# Sheet1.net
KiCad netlist of a schematic drawn in Altium Designer
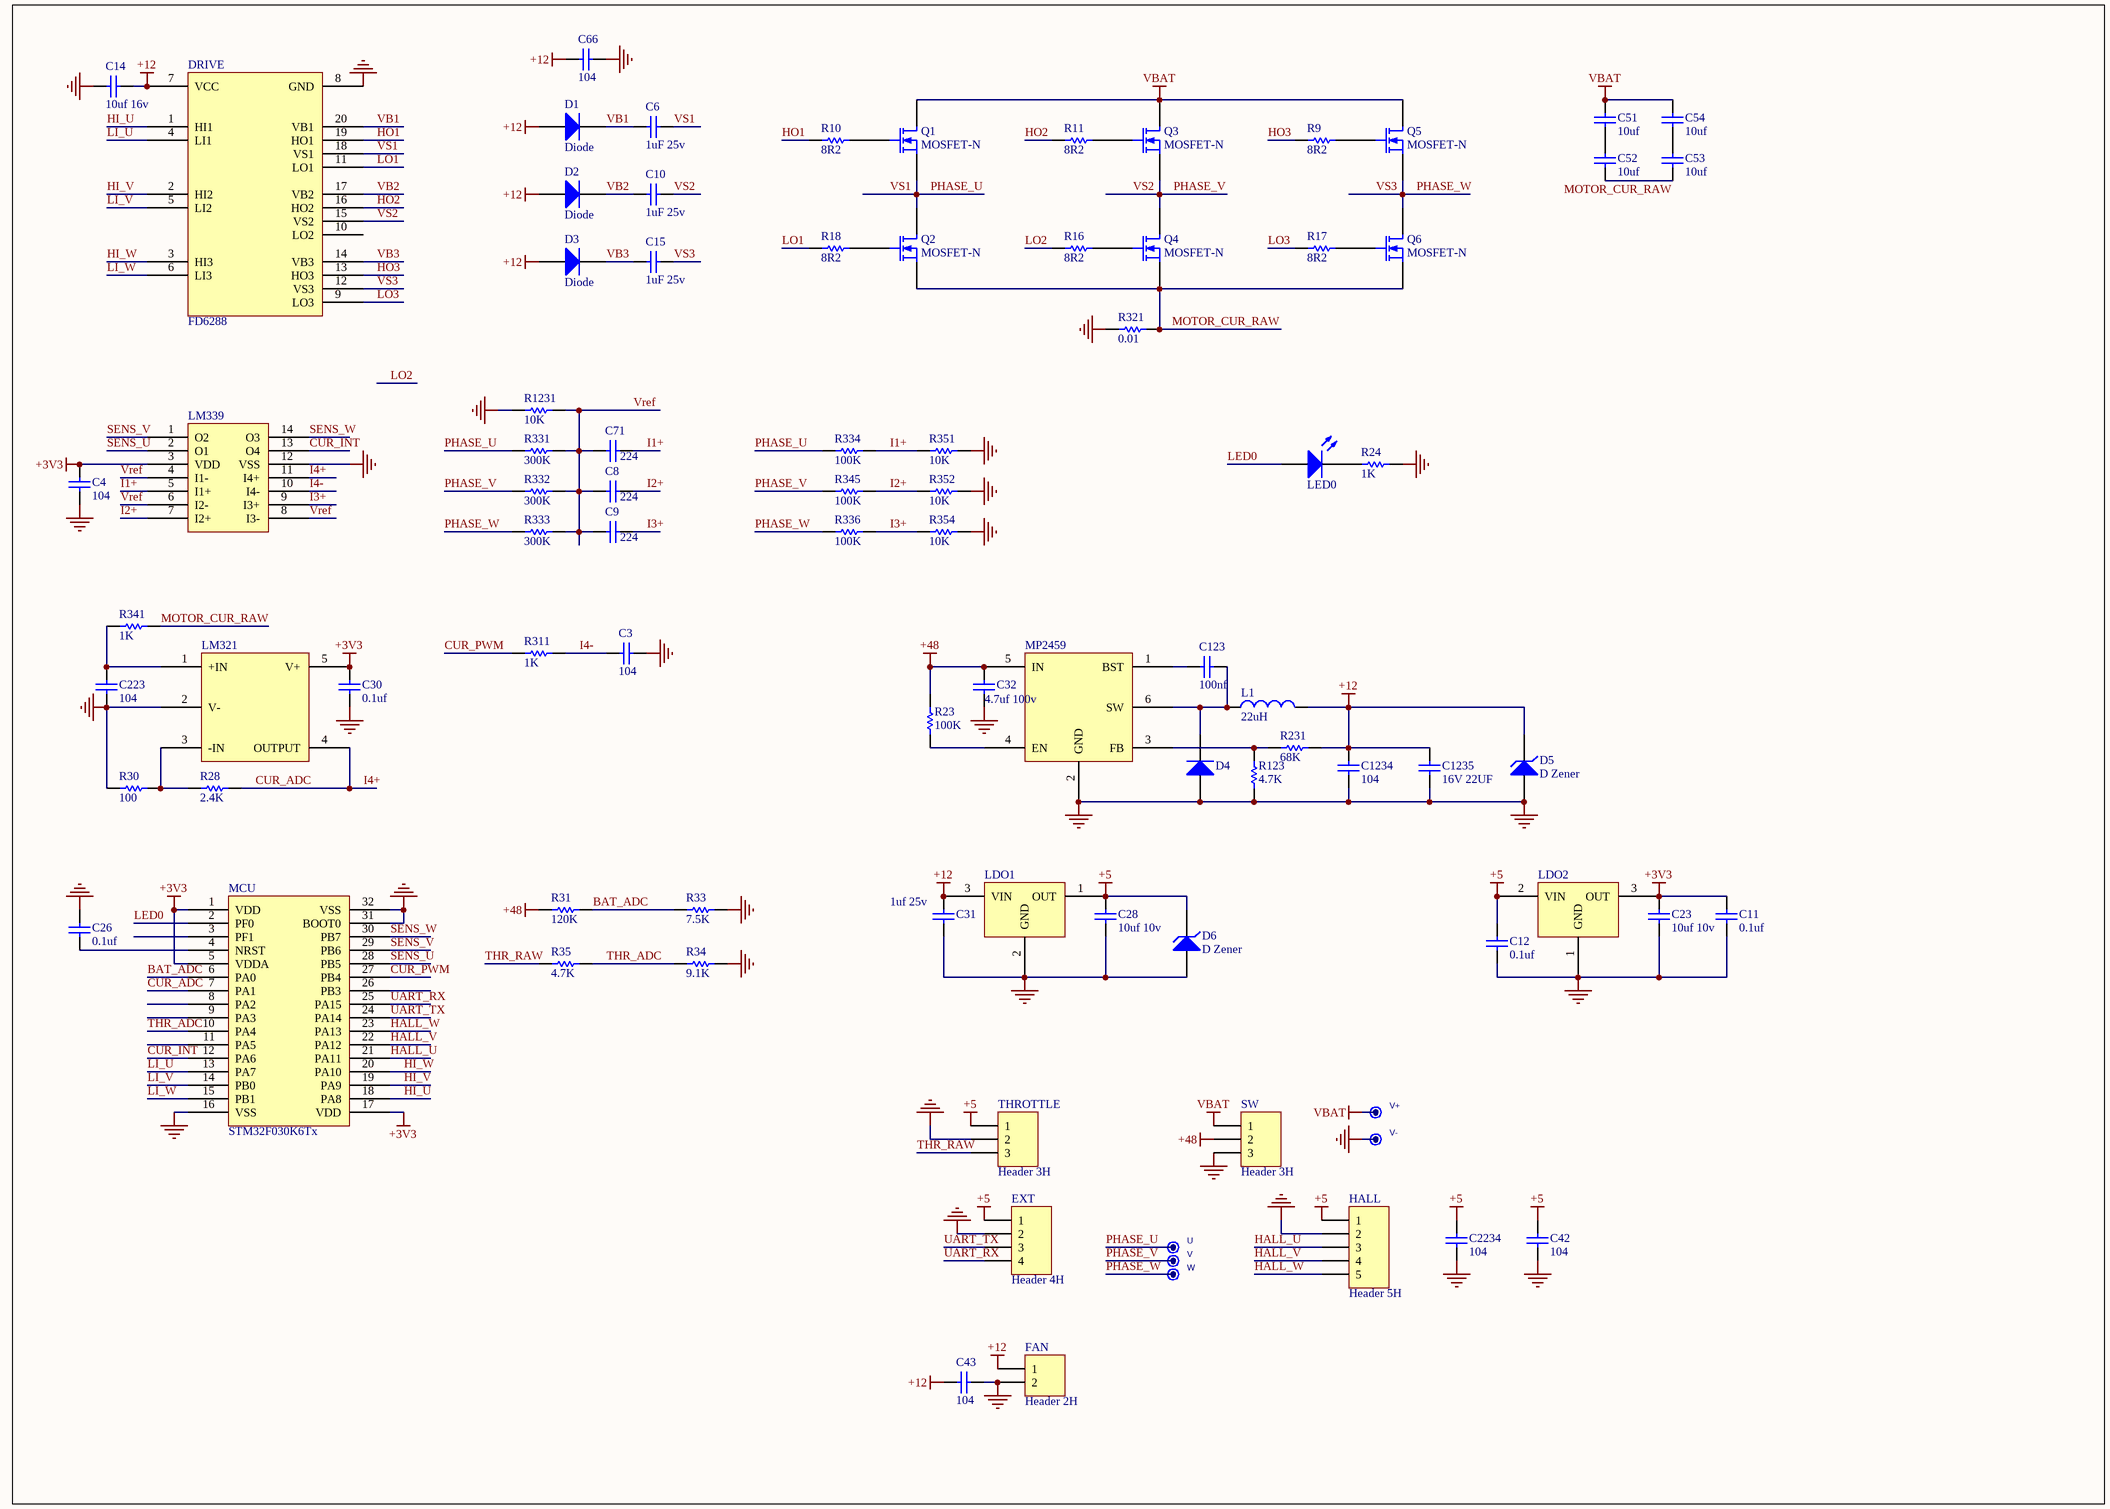
[diagram p0: Sheet1.SchDoc]

(export (version "E")
  (design (tool "Eeschema 10.0.6"))
  (components
    (comp (ref "C3")
      (value "104")
      (footprint "0603")
      (description "Capacitor")
      (fields (field (name "Comment") "Cap") (field (name "PUBLISHER") "Altium Limited"))
      (libsource (lib "Miscellaneous Devices") (part "Cap"))
    )
    (comp (ref "C4")
      (value "104")
      (footprint "0603")
      (description "Capacitor")
      (fields (field (name "Comment") "Cap") (field (name "PUBLISHER") "Altium Limited"))
      (libsource (lib "Miscellaneous Devices") (part "Cap"))
    )
    (comp (ref "C6")
      (value "1uF 25v")
      (footprint "0603")
      (description "Capacitor")
      (fields (field (name "Comment") "Cap") (field (name "PUBLISHER") "Altium Limited"))
      (libsource (lib "Miscellaneous Devices") (part "Cap"))
    )
    (comp (ref "C8")
      (value "224")
      (footprint "0603")
      (description "Capacitor")
      (fields (field (name "Comment") "Cap") (field (name "PUBLISHER") "Altium Limited"))
      (libsource (lib "Miscellaneous Devices") (part "Cap"))
    )
    (comp (ref "C9")
      (value "224")
      (footprint "0603")
      (description "Capacitor")
      (fields (field (name "Comment") "Cap") (field (name "PUBLISHER") "Altium Limited"))
      (libsource (lib "Miscellaneous Devices") (part "Cap"))
    )
    (comp (ref "C10")
      (value "1uF 25v")
      (footprint "0603")
      (description "Capacitor")
      (fields (field (name "Comment") "Cap") (field (name "PUBLISHER") "Altium Limited"))
      (libsource (lib "Miscellaneous Devices") (part "Cap"))
    )
    (comp (ref "C11")
      (value "0.1uf")
      (footprint "0603")
      (description "Capacitor")
      (fields (field (name "Comment") "Cap") (field (name "PUBLISHER") "Altium Limited"))
      (libsource (lib "Miscellaneous Devices") (part "Cap"))
    )
    (comp (ref "C12")
      (value "0.1uf")
      (footprint "0603")
      (description "Capacitor")
      (fields (field (name "Comment") "Cap") (field (name "PUBLISHER") "Altium Limited"))
      (libsource (lib "Miscellaneous Devices") (part "Cap"))
    )
    (comp (ref "C14")
      (value "10uf 16v")
      (footprint "0603")
      (description "Capacitor")
      (fields (field (name "Comment") "Cap") (field (name "PUBLISHER") "Altium Limited"))
      (libsource (lib "Miscellaneous Devices") (part "Cap"))
    )
    (comp (ref "C15")
      (value "1uF 25v")
      (footprint "0603")
      (description "Capacitor")
      (fields (field (name "Comment") "Cap") (field (name "PUBLISHER") "Altium Limited"))
      (libsource (lib "Miscellaneous Devices") (part "Cap"))
    )
    (comp (ref "C23")
      (value "10uf 10v")
      (footprint "0603")
      (description "Capacitor")
      (fields (field (name "Comment") "Cap") (field (name "PUBLISHER") "Altium Limited"))
      (libsource (lib "Miscellaneous Devices") (part "Cap"))
    )
    (comp (ref "C26")
      (value "0.1uf")
      (footprint "0603")
      (description "Capacitor")
      (fields (field (name "Comment") "Cap") (field (name "PUBLISHER") "Altium Limited"))
      (libsource (lib "Miscellaneous Devices") (part "Cap"))
    )
    (comp (ref "C28")
      (value "10uf 10v")
      (footprint "0603")
      (description "Capacitor")
      (fields (field (name "Comment") "Cap") (field (name "PUBLISHER") "Altium Limited"))
      (libsource (lib "Miscellaneous Devices") (part "Cap"))
    )
    (comp (ref "C30")
      (value "0.1uf")
      (footprint "0603")
      (description "Capacitor")
      (fields (field (name "Comment") "Cap") (field (name "PUBLISHER") "Altium Limited"))
      (libsource (lib "Miscellaneous Devices") (part "Cap"))
    )
    (comp (ref "C31")
      (value "1uf 25v")
      (footprint "0603")
      (description "Capacitor")
      (fields (field (name "Comment") "Cap") (field (name "PUBLISHER") "Altium Limited"))
      (libsource (lib "Miscellaneous Devices") (part "Cap"))
    )
    (comp (ref "C32")
      (value "4.7uf 100v")
      (footprint "1206")
      (description "Capacitor")
      (fields (field (name "Comment") "Cap") (field (name "PUBLISHER") "Altium Limited"))
      (libsource (lib "Miscellaneous Devices") (part "Cap"))
    )
    (comp (ref "C42")
      (value "104")
      (footprint "0603")
      (description "Capacitor")
      (fields (field (name "Comment") "Cap") (field (name "PUBLISHER") "Altium Limited"))
      (libsource (lib "Miscellaneous Devices") (part "Cap"))
    )
    (comp (ref "C43")
      (value "104")
      (footprint "0603")
      (description "Capacitor")
      (fields (field (name "Comment") "Cap") (field (name "PUBLISHER") "Altium Limited"))
      (libsource (lib "Miscellaneous Devices") (part "Cap"))
    )
    (comp (ref "C51")
      (value "10uf")
      (footprint "1206")
      (description "Capacitor")
      (fields (field (name "Comment") "Cap") (field (name "PUBLISHER") "Altium Limited"))
      (libsource (lib "Miscellaneous Devices") (part "Cap"))
    )
    (comp (ref "C52")
      (value "10uf")
      (footprint "1206")
      (description "Capacitor")
      (fields (field (name "Comment") "Cap") (field (name "PUBLISHER") "Altium Limited"))
      (libsource (lib "Miscellaneous Devices") (part "Cap"))
    )
    (comp (ref "C53")
      (value "10uf")
      (footprint "1206")
      (description "Capacitor")
      (fields (field (name "Comment") "Cap") (field (name "PUBLISHER") "Altium Limited"))
      (libsource (lib "Miscellaneous Devices") (part "Cap"))
    )
    (comp (ref "C54")
      (value "10uf")
      (footprint "1206")
      (description "Capacitor")
      (fields (field (name "Comment") "Cap") (field (name "PUBLISHER") "Altium Limited"))
      (libsource (lib "Miscellaneous Devices") (part "Cap"))
    )
    (comp (ref "C66")
      (value "104")
      (footprint "0603")
      (description "Capacitor")
      (fields (field (name "Comment") "Cap") (field (name "PUBLISHER") "Altium Limited"))
      (libsource (lib "Miscellaneous Devices") (part "Cap"))
    )
    (comp (ref "C71")
      (value "224")
      (footprint "0603")
      (description "Capacitor")
      (fields (field (name "Comment") "Cap") (field (name "PUBLISHER") "Altium Limited"))
      (libsource (lib "Miscellaneous Devices") (part "Cap"))
    )
    (comp (ref "C123")
      (value "100nf")
      (footprint "0603")
      (description "Capacitor")
      (fields (field (name "Comment") "Cap") (field (name "PUBLISHER") "Altium Limited"))
      (libsource (lib "Miscellaneous Devices") (part "Cap"))
    )
    (comp (ref "C223")
      (value "104")
      (footprint "0603")
      (description "Capacitor")
      (fields (field (name "Comment") "Cap") (field (name "PUBLISHER") "Altium Limited"))
      (libsource (lib "Miscellaneous Devices") (part "Cap"))
    )
    (comp (ref "C1234")
      (value "104")
      (footprint "0603")
      (description "Capacitor")
      (fields (field (name "Comment") "Cap") (field (name "PUBLISHER") "Altium Limited"))
      (libsource (lib "Miscellaneous Devices") (part "Cap"))
    )
    (comp (ref "C1235")
      (value "16V 22UF")
      (footprint "1206")
      (description "Capacitor")
      (fields (field (name "Comment") "Cap") (field (name "PUBLISHER") "Altium Limited"))
      (libsource (lib "Miscellaneous Devices") (part "Cap"))
    )
    (comp (ref "C2234")
      (value "104")
      (footprint "0603")
      (description "Capacitor")
      (fields (field (name "Comment") "Cap") (field (name "PUBLISHER") "Altium Limited"))
      (libsource (lib "Miscellaneous Devices") (part "Cap"))
    )
    (comp (ref "D1")
      (value "Diode")
      (footprint "0603")
      (description "Default Diode")
      (fields (field (name "PUBLISHER") "Altium Limited"))
      (libsource (lib "Miscellaneous Devices") (part "Diode"))
    )
    (comp (ref "D2")
      (value "Diode")
      (footprint "0603")
      (description "Default Diode")
      (fields (field (name "PUBLISHER") "Altium Limited"))
      (libsource (lib "Miscellaneous Devices") (part "Diode"))
    )
    (comp (ref "D3")
      (value "Diode")
      (footprint "0603")
      (description "Default Diode")
      (fields (field (name "PUBLISHER") "Altium Limited"))
      (libsource (lib "Miscellaneous Devices") (part "Diode"))
    )
    (comp (ref "D4")
      (value "Diode")
      (footprint "1206")
      (description "Default Diode")
      (fields (field (name "PUBLISHER") "Altium Limited"))
      (libsource (lib "Miscellaneous Devices") (part "Diode"))
    )
    (comp (ref "D5")
      (value "D Zener")
      (footprint "1206")
      (description "Zener Diode")
      (fields (field (name "PUBLISHER") "Altium Limited"))
      (libsource (lib "Miscellaneous Devices") (part "D Zener"))
    )
    (comp (ref "D6")
      (value "D Zener")
      (footprint "1206")
      (description "Zener Diode")
      (fields (field (name "PUBLISHER") "Altium Limited"))
      (libsource (lib "Miscellaneous Devices") (part "D Zener"))
    )
    (comp (ref "DRIVE") (value "FD6288") (footprint "TSSOP20") (libsource (lib "Schlib1") (part "FD6288")))
    (comp (ref "EXT")
      (value "Header 4H")
      (footprint "HDR1X4H")
      (description "Header, 4-Pin, Right Angle")
      (fields (field (name "PUBLISHER") "Altium Limited"))
      (libsource (lib "Miscellaneous Connectors") (part "Header 4H"))
    )
    (comp (ref "FAN")
      (value "Header 2H")
      (footprint "HDR1X2H")
      (description "Header, 2-Pin, Right Angle")
      (fields (field (name "PUBLISHER") "Altium Limited"))
      (libsource (lib "Miscellaneous Connectors") (part "Header 2H"))
    )
    (comp (ref "HALL")
      (value "Header 5H")
      (footprint "HDR1X5H")
      (description "Header, 5-Pin, Right Angle")
      (fields (field (name "PUBLISHER") "Altium Limited"))
      (libsource (lib "Miscellaneous Connectors") (part "Header 5H"))
    )
    (comp (ref "L1")
      (value "22uH")
      (footprint "CDRH4D28")
      (description "Inductor")
      (fields (field (name "PUBLISHER") "Altium Limited"))
      (libsource (lib "Miscellaneous Devices") (part "Inductor"))
    )
    (comp (ref "LDO1") (value "78L05") (footprint "SOT-89") (libsource (lib "Schlib1") (part "78L05")))
    (comp (ref "LDO2") (value "XC6206") (footprint "SOT23") (libsource (lib "Schlib1") (part "HT75xx")))
    (comp (ref "LED")
      (value "LED0")
      (footprint "0603")
      (description "Typical INFRARED GaAs LED")
      (fields (field (name "PUBLISHER") "Altium Limited"))
      (libsource (lib "Miscellaneous Devices") (part "LED0"))
    )
    (comp (ref "LM321") (value "LM321") (footprint "SOT23-5") (libsource (lib "Schlib1") (part "LM321")))
    (comp (ref "LM339") (value "LM339") (footprint "SOP14") (libsource (lib "Schlib1") (part "LM339")))
    (comp (ref "MCU")
      (value "STM32F030K6Tx")
      (footprint "LQFP-32")
      (libsource (lib "Schlib1") (part "STM32F030K6Tx"))
    )
    (comp (ref "MP2459") (value "MP2459") (footprint "SOT23-6") (libsource (lib "Schlib1") (part "MP2459")))
    (comp (ref "Q1")
      (value "MOSFET-N")
      (footprint "TO220-MIX")
      (description "N-Channel MOSFET")
      (fields (field (name "PUBLISHER") "Altium Limited"))
      (libsource (lib "Miscellaneous Devices") (part "MOSFET-N"))
    )
    (comp (ref "Q2")
      (value "MOSFET-N")
      (footprint "TO220-MIX")
      (description "N-Channel MOSFET")
      (fields (field (name "PUBLISHER") "Altium Limited"))
      (libsource (lib "Miscellaneous Devices") (part "MOSFET-N"))
    )
    (comp (ref "Q3")
      (value "MOSFET-N")
      (footprint "TO220-MIX")
      (description "N-Channel MOSFET")
      (fields (field (name "PUBLISHER") "Altium Limited"))
      (libsource (lib "Miscellaneous Devices") (part "MOSFET-N"))
    )
    (comp (ref "Q4")
      (value "MOSFET-N")
      (footprint "TO220-MIX")
      (description "N-Channel MOSFET")
      (fields (field (name "PUBLISHER") "Altium Limited"))
      (libsource (lib "Miscellaneous Devices") (part "MOSFET-N"))
    )
    (comp (ref "Q5")
      (value "MOSFET-N")
      (footprint "TO220-MIX")
      (description "N-Channel MOSFET")
      (fields (field (name "PUBLISHER") "Altium Limited"))
      (libsource (lib "Miscellaneous Devices") (part "MOSFET-N"))
    )
    (comp (ref "Q6")
      (value "MOSFET-N")
      (footprint "TO220-MIX")
      (description "N-Channel MOSFET")
      (fields (field (name "PUBLISHER") "Altium Limited"))
      (libsource (lib "Miscellaneous Devices") (part "MOSFET-N"))
    )
    (comp (ref "R9")
      (value "8R2")
      (footprint "0603")
      (description "Resistor")
      (fields (field (name "Comment") "Res1") (field (name "PUBLISHER") "Altium Limited"))
      (libsource (lib "Miscellaneous Devices") (part "Res1"))
    )
    (comp (ref "R10")
      (value "8R2")
      (footprint "0603")
      (description "Resistor")
      (fields (field (name "Comment") "Res1") (field (name "PUBLISHER") "Altium Limited"))
      (libsource (lib "Miscellaneous Devices") (part "Res1"))
    )
    (comp (ref "R11")
      (value "8R2")
      (footprint "0603")
      (description "Resistor")
      (fields (field (name "Comment") "Res1") (field (name "PUBLISHER") "Altium Limited"))
      (libsource (lib "Miscellaneous Devices") (part "Res1"))
    )
    (comp (ref "R16")
      (value "8R2")
      (footprint "0603")
      (description "Resistor")
      (fields (field (name "Comment") "Res1") (field (name "PUBLISHER") "Altium Limited"))
      (libsource (lib "Miscellaneous Devices") (part "Res1"))
    )
    (comp (ref "R17")
      (value "8R2")
      (footprint "0603")
      (description "Resistor")
      (fields (field (name "Comment") "Res1") (field (name "PUBLISHER") "Altium Limited"))
      (libsource (lib "Miscellaneous Devices") (part "Res1"))
    )
    (comp (ref "R18")
      (value "8R2")
      (footprint "0603")
      (description "Resistor")
      (fields (field (name "Comment") "Res1") (field (name "PUBLISHER") "Altium Limited"))
      (libsource (lib "Miscellaneous Devices") (part "Res1"))
    )
    (comp (ref "R23")
      (value "100K")
      (footprint "0603")
      (description "Resistor")
      (fields (field (name "Comment") "Res1") (field (name "PUBLISHER") "Altium Limited"))
      (libsource (lib "Miscellaneous Devices") (part "Res1"))
    )
    (comp (ref "R24")
      (value "1K")
      (footprint "0603")
      (description "Resistor")
      (fields (field (name "Comment") "Res1") (field (name "PUBLISHER") "Altium Limited"))
      (libsource (lib "Miscellaneous Devices") (part "Res1"))
    )
    (comp (ref "R28")
      (value "2.4K")
      (footprint "0603")
      (description "Resistor")
      (fields (field (name "Comment") "Res1") (field (name "PUBLISHER") "Altium Limited"))
      (libsource (lib "Miscellaneous Devices") (part "Res1"))
    )
    (comp (ref "R30")
      (value "100")
      (footprint "0603")
      (description "Resistor")
      (fields (field (name "Comment") "Res1") (field (name "PUBLISHER") "Altium Limited"))
      (libsource (lib "Miscellaneous Devices") (part "Res1"))
    )
    (comp (ref "R31")
      (value "120K")
      (footprint "0603")
      (description "Resistor")
      (fields (field (name "Comment") "Res1") (field (name "PUBLISHER") "Altium Limited"))
      (libsource (lib "Miscellaneous Devices") (part "Res1"))
    )
    (comp (ref "R33")
      (value "7.5K")
      (footprint "0603")
      (description "Resistor")
      (fields (field (name "Comment") "Res1") (field (name "PUBLISHER") "Altium Limited"))
      (libsource (lib "Miscellaneous Devices") (part "Res1"))
    )
    (comp (ref "R34")
      (value "9.1K")
      (footprint "0603")
      (description "Resistor")
      (fields (field (name "Comment") "Res1") (field (name "PUBLISHER") "Altium Limited"))
      (libsource (lib "Miscellaneous Devices") (part "Res1"))
    )
    (comp (ref "R35")
      (value "4.7K")
      (footprint "0603")
      (description "Resistor")
      (fields (field (name "Comment") "Res1") (field (name "PUBLISHER") "Altium Limited"))
      (libsource (lib "Miscellaneous Devices") (part "Res1"))
    )
    (comp (ref "R123")
      (value "4.7K")
      (footprint "0603")
      (description "Resistor")
      (fields (field (name "Comment") "Res1") (field (name "PUBLISHER") "Altium Limited"))
      (libsource (lib "Miscellaneous Devices") (part "Res1"))
    )
    (comp (ref "R231")
      (value "68K")
      (footprint "0603")
      (description "Resistor")
      (fields (field (name "Comment") "Res1") (field (name "PUBLISHER") "Altium Limited"))
      (libsource (lib "Miscellaneous Devices") (part "Res1"))
    )
    (comp (ref "R311")
      (value "1K")
      (footprint "0603")
      (description "Resistor")
      (fields (field (name "Comment") "Res1") (field (name "PUBLISHER") "Altium Limited"))
      (libsource (lib "Miscellaneous Devices") (part "Res1"))
    )
    (comp (ref "R321")
      (value "0.01")
      (footprint "1206")
      (description "Resistor")
      (fields (field (name "Comment") "Res1") (field (name "PUBLISHER") "Altium Limited"))
      (libsource (lib "Miscellaneous Devices") (part "Res1"))
    )
    (comp (ref "R331")
      (value "300K")
      (footprint "0603")
      (description "Resistor")
      (fields (field (name "Comment") "Res1") (field (name "PUBLISHER") "Altium Limited"))
      (libsource (lib "Miscellaneous Devices") (part "Res1"))
    )
    (comp (ref "R332")
      (value "300K")
      (footprint "0603")
      (description "Resistor")
      (fields (field (name "Comment") "Res1") (field (name "PUBLISHER") "Altium Limited"))
      (libsource (lib "Miscellaneous Devices") (part "Res1"))
    )
    (comp (ref "R333")
      (value "300K")
      (footprint "0603")
      (description "Resistor")
      (fields (field (name "Comment") "Res1") (field (name "PUBLISHER") "Altium Limited"))
      (libsource (lib "Miscellaneous Devices") (part "Res1"))
    )
    (comp (ref "R334")
      (value "100K")
      (footprint "0603")
      (description "Resistor")
      (fields (field (name "Comment") "Res1") (field (name "PUBLISHER") "Altium Limited"))
      (libsource (lib "Miscellaneous Devices") (part "Res1"))
    )
    (comp (ref "R336")
      (value "100K")
      (footprint "0603")
      (description "Resistor")
      (fields (field (name "Comment") "Res1") (field (name "PUBLISHER") "Altium Limited"))
      (libsource (lib "Miscellaneous Devices") (part "Res1"))
    )
    (comp (ref "R341")
      (value "1K")
      (footprint "0603")
      (description "Resistor")
      (fields (field (name "Comment") "Res1") (field (name "PUBLISHER") "Altium Limited"))
      (libsource (lib "Miscellaneous Devices") (part "Res1"))
    )
    (comp (ref "R345")
      (value "100K")
      (footprint "0603")
      (description "Resistor")
      (fields (field (name "Comment") "Res1") (field (name "PUBLISHER") "Altium Limited"))
      (libsource (lib "Miscellaneous Devices") (part "Res1"))
    )
    (comp (ref "R351")
      (value "10K")
      (footprint "0603")
      (description "Resistor")
      (fields (field (name "Comment") "Res1") (field (name "PUBLISHER") "Altium Limited"))
      (libsource (lib "Miscellaneous Devices") (part "Res1"))
    )
    (comp (ref "R352")
      (value "10K")
      (footprint "0603")
      (description "Resistor")
      (fields (field (name "Comment") "Res1") (field (name "PUBLISHER") "Altium Limited"))
      (libsource (lib "Miscellaneous Devices") (part "Res1"))
    )
    (comp (ref "R354")
      (value "10K")
      (footprint "0603")
      (description "Resistor")
      (fields (field (name "Comment") "Res1") (field (name "PUBLISHER") "Altium Limited"))
      (libsource (lib "Miscellaneous Devices") (part "Res1"))
    )
    (comp (ref "R1231")
      (value "10K")
      (footprint "0603")
      (description "Resistor")
      (fields (field (name "Comment") "Res1") (field (name "PUBLISHER") "Altium Limited"))
      (libsource (lib "Miscellaneous Devices") (part "Res1"))
    )
    (comp (ref "SW")
      (value "Header 3H")
      (footprint "HDR1X3H")
      (description "Header, 3-Pin, Right Angle")
      (fields (field (name "PUBLISHER") "Altium Limited"))
      (libsource (lib "Miscellaneous Connectors") (part "Header 3H"))
    )
    (comp (ref "THROTTLE")
      (value "Header 3H")
      (footprint "HDR1X3H")
      (description "Header, 3-Pin, Right Angle")
      (fields (field (name "PUBLISHER") "Altium Limited"))
      (libsource (lib "Miscellaneous Connectors") (part "Header 3H"))
    )
    (comp (ref "U")
      (value "TPS50mil")
      (footprint "PHASE")
      (description "Test Point, 12x25mil, Not Populated")
      (libsource (lib "mis") (part "TPS50mil"))
    )
    (comp (ref "V")
      (value "TPS50mil")
      (footprint "PHASE")
      (description "Test Point, 12x25mil, Not Populated")
      (libsource (lib "mis") (part "TPS50mil"))
    )
    (comp (ref "V+")
      (value "TPS50mil")
      (footprint "PHASE")
      (description "Test Point, 12x25mil, Not Populated")
      (libsource (lib "mis") (part "TPS50mil"))
    )
    (comp (ref "V-")
      (value "TPS50mil")
      (footprint "PHASE")
      (description "Test Point, 12x25mil, Not Populated")
      (libsource (lib "mis") (part "TPS50mil"))
    )
    (comp (ref "W")
      (value "TPS50mil")
      (footprint "PHASE")
      (description "Test Point, 12x25mil, Not Populated")
      (libsource (lib "mis") (part "TPS50mil"))
    )
  )
  (nets
    (net (code "1") (name "+3V3") (class "Default")
      (node (ref "C11") (pin "1") (pinfunction "1_1") (pintype "passive"))
      (node (ref "C23") (pin "1") (pinfunction "1_1") (pintype "passive"))
      (node (ref "C30") (pin "1") (pinfunction "1_1") (pintype "passive"))
      (node (ref "C4") (pin "2") (pinfunction "2_2") (pintype "passive"))
      (node (ref "LDO2") (pin "3") (pinfunction "OUT_3") (pintype "passive"))
      (node (ref "LM321") (pin "5") (pinfunction "V+_5") (pintype "passive"))
      (node (ref "LM339") (pin "3") (pinfunction "VDD_3") (pintype "passive"))
      (node (ref "MCU") (pin "1") (pinfunction "VDD_1") (pintype "passive"))
      (node (ref "MCU") (pin "17") (pinfunction "VDD_17") (pintype "passive"))
      (node (ref "MCU") (pin "5") (pinfunction "VDDA_5") (pintype "passive"))
    )
    (net (code "2") (name "+5") (class "Default")
      (node (ref "C12") (pin "1") (pinfunction "1_1") (pintype "passive"))
      (node (ref "C2234") (pin "1") (pinfunction "1_1") (pintype "passive"))
      (node (ref "C28") (pin "1") (pinfunction "1_1") (pintype "passive"))
      (node (ref "C42") (pin "1") (pinfunction "1_1") (pintype "passive"))
      (node (ref "D6") (pin "2") (pinfunction "K_2") (pintype "passive"))
      (node (ref "EXT") (pin "1") (pinfunction "1_1") (pintype "passive"))
      (node (ref "HALL") (pin "1") (pinfunction "1_1") (pintype "passive"))
      (node (ref "LDO1") (pin "1") (pinfunction "OUT_1") (pintype "passive"))
      (node (ref "LDO2") (pin "2") (pinfunction "VIN_2") (pintype "passive"))
      (node (ref "THROTTLE") (pin "1") (pinfunction "1_1") (pintype "passive"))
    )
    (net (code "3") (name "+12") (class "Default")
      (node (ref "C1234") (pin "1") (pinfunction "1_1") (pintype "passive"))
      (node (ref "C1235") (pin "1") (pinfunction "1_1") (pintype "passive"))
      (node (ref "C14") (pin "2") (pinfunction "2_2") (pintype "passive"))
      (node (ref "C31") (pin "1") (pinfunction "1_1") (pintype "passive"))
      (node (ref "C43") (pin "1") (pinfunction "1_1") (pintype "passive"))
      (node (ref "C66") (pin "1") (pinfunction "1_1") (pintype "passive"))
      (node (ref "D1") (pin "1") (pinfunction "A_1") (pintype "passive"))
      (node (ref "D2") (pin "1") (pinfunction "A_1") (pintype "passive"))
      (node (ref "D3") (pin "1") (pinfunction "A_1") (pintype "passive"))
      (node (ref "D5") (pin "2") (pinfunction "K_2") (pintype "passive"))
      (node (ref "DRIVE") (pin "7") (pinfunction "VCC_7") (pintype "passive"))
      (node (ref "FAN") (pin "1") (pinfunction "1_1") (pintype "passive"))
      (node (ref "L1") (pin "2") (pinfunction "2_2") (pintype "passive"))
      (node (ref "LDO1") (pin "3") (pinfunction "VIN_3") (pintype "passive"))
      (node (ref "R231") (pin "2") (pinfunction "2_2") (pintype "passive"))
    )
    (net (code "4") (name "+48") (class "Default")
      (node (ref "C32") (pin "1") (pinfunction "1_1") (pintype "passive"))
      (node (ref "MP2459") (pin "5") (pinfunction "IN_5") (pintype "passive"))
      (node (ref "R23") (pin "1") (pinfunction "1_1") (pintype "passive"))
      (node (ref "R31") (pin "1") (pinfunction "1_1") (pintype "passive"))
      (node (ref "SW") (pin "2") (pinfunction "2_2") (pintype "passive"))
    )
    (net (code "5") (name "/BAT_ADC") (class "Default")
      (node (ref "MCU") (pin "6") (pinfunction "PA0_6") (pintype "passive"))
      (node (ref "R31") (pin "2") (pinfunction "2_2") (pintype "passive"))
      (node (ref "R33") (pin "1") (pinfunction "1_1") (pintype "passive"))
    )
    (net (code "6") (name "/CUR_ADC") (class "Default")
      (node (ref "LM321") (pin "4") (pinfunction "OUTPUT_4") (pintype "passive"))
      (node (ref "LM339") (pin "11") (pinfunction "I4+_11") (pintype "passive"))
      (node (ref "MCU") (pin "7") (pinfunction "PA1_7") (pintype "passive"))
      (node (ref "R28") (pin "2") (pinfunction "2_2") (pintype "passive"))
    )
    (net (code "7") (name "/CUR_INT") (class "Default")
      (node (ref "LM339") (pin "13") (pinfunction "O4_13") (pintype "passive"))
      (node (ref "MCU") (pin "12") (pinfunction "PA6_12") (pintype "passive"))
    )
    (net (code "8") (name "/CUR_PWM") (class "Default")
      (node (ref "MCU") (pin "27") (pinfunction "PB4_27") (pintype "passive"))
      (node (ref "R311") (pin "2") (pinfunction "2_2") (pintype "passive"))
    )
    (net (code "9") (name "/HALL_U") (class "Default")
      (node (ref "HALL") (pin "3") (pinfunction "3_3") (pintype "passive"))
      (node (ref "MCU") (pin "21") (pinfunction "PA11_21") (pintype "passive"))
    )
    (net (code "10") (name "/HALL_V") (class "Default")
      (node (ref "HALL") (pin "4") (pinfunction "4_4") (pintype "passive"))
      (node (ref "MCU") (pin "22") (pinfunction "PA12_22") (pintype "passive"))
    )
    (net (code "11") (name "/HALL_W") (class "Default")
      (node (ref "HALL") (pin "5") (pinfunction "5_5") (pintype "passive"))
      (node (ref "MCU") (pin "23") (pinfunction "PA13_23") (pintype "passive"))
    )
    (net (code "12") (name "/HI_U") (class "Default")
      (node (ref "DRIVE") (pin "1") (pinfunction "HI1_1") (pintype "passive"))
      (node (ref "MCU") (pin "18") (pinfunction "PA8_18") (pintype "passive"))
    )
    (net (code "13") (name "/HI_V") (class "Default")
      (node (ref "DRIVE") (pin "2") (pinfunction "HI2_2") (pintype "passive"))
      (node (ref "MCU") (pin "19") (pinfunction "PA9_19") (pintype "passive"))
    )
    (net (code "14") (name "/HI_W") (class "Default")
      (node (ref "DRIVE") (pin "3") (pinfunction "HI3_3") (pintype "passive"))
      (node (ref "MCU") (pin "20") (pinfunction "PA10_20") (pintype "passive"))
    )
    (net (code "15") (name "/HO1") (class "Default")
      (node (ref "DRIVE") (pin "19") (pinfunction "HO1_19") (pintype "passive"))
      (node (ref "R10") (pin "2") (pinfunction "2_2") (pintype "passive"))
    )
    (net (code "16") (name "/HO2") (class "Default")
      (node (ref "DRIVE") (pin "16") (pinfunction "HO2_16") (pintype "passive"))
      (node (ref "R11") (pin "2") (pinfunction "2_2") (pintype "passive"))
    )
    (net (code "17") (name "/HO3") (class "Default")
      (node (ref "DRIVE") (pin "13") (pinfunction "HO3_13") (pintype "passive"))
      (node (ref "R9") (pin "2") (pinfunction "2_2") (pintype "passive"))
    )
    (net (code "18") (name "/I1+") (class "Default")
      (node (ref "C71") (pin "1") (pinfunction "1_1") (pintype "passive"))
      (node (ref "LM339") (pin "5") (pinfunction "I1+_5") (pintype "passive"))
      (node (ref "R334") (pin "2") (pinfunction "2_2") (pintype "passive"))
      (node (ref "R351") (pin "2") (pinfunction "2_2") (pintype "passive"))
    )
    (net (code "19") (name "/I2+") (class "Default")
      (node (ref "C8") (pin "1") (pinfunction "1_1") (pintype "passive"))
      (node (ref "LM339") (pin "7") (pinfunction "I2+_7") (pintype "passive"))
      (node (ref "R345") (pin "2") (pinfunction "2_2") (pintype "passive"))
      (node (ref "R352") (pin "2") (pinfunction "2_2") (pintype "passive"))
    )
    (net (code "20") (name "/I3+") (class "Default")
      (node (ref "C9") (pin "1") (pinfunction "1_1") (pintype "passive"))
      (node (ref "LM339") (pin "9") (pinfunction "I3+_9") (pintype "passive"))
      (node (ref "R336") (pin "2") (pinfunction "2_2") (pintype "passive"))
      (node (ref "R354") (pin "2") (pinfunction "2_2") (pintype "passive"))
    )
    (net (code "21") (name "/I4-") (class "Default")
      (node (ref "C3") (pin "1") (pinfunction "1_1") (pintype "passive"))
      (node (ref "LM339") (pin "10") (pinfunction "I4-_10") (pintype "passive"))
      (node (ref "R311") (pin "1") (pinfunction "1_1") (pintype "passive"))
    )
    (net (code "22") (name "/LED0") (class "Default")
      (node (ref "LED") (pin "1") (pinfunction "A_1") (pintype "passive"))
      (node (ref "MCU") (pin "2") (pinfunction "PF0_2") (pintype "passive"))
    )
    (net (code "23") (name "/LI_U") (class "Default")
      (node (ref "DRIVE") (pin "4") (pinfunction "LI1_4") (pintype "passive"))
      (node (ref "MCU") (pin "13") (pinfunction "PA7_13") (pintype "passive"))
    )
    (net (code "24") (name "/LI_V") (class "Default")
      (node (ref "DRIVE") (pin "5") (pinfunction "LI2_5") (pintype "passive"))
      (node (ref "MCU") (pin "14") (pinfunction "PB0_14") (pintype "passive"))
    )
    (net (code "25") (name "/LI_W") (class "Default")
      (node (ref "DRIVE") (pin "6") (pinfunction "LI3_6") (pintype "passive"))
      (node (ref "MCU") (pin "15") (pinfunction "PB1_15") (pintype "passive"))
    )
    (net (code "26") (name "/LO1") (class "Default")
      (node (ref "DRIVE") (pin "11") (pinfunction "LO1_11") (pintype "passive"))
      (node (ref "R18") (pin "2") (pinfunction "2_2") (pintype "passive"))
    )
    (net (code "27") (name "/LO2") (class "Default")
      (node (ref "R16") (pin "2") (pinfunction "2_2") (pintype "passive"))
    )
    (net (code "28") (name "/LO3") (class "Default")
      (node (ref "DRIVE") (pin "9") (pinfunction "LO3_9") (pintype "passive"))
      (node (ref "R17") (pin "2") (pinfunction "2_2") (pintype "passive"))
    )
    (net (code "29") (name "/MOTOR_CUR_RAW") (class "Default")
      (node (ref "C52") (pin "2") (pinfunction "2_2") (pintype "passive"))
      (node (ref "C53") (pin "2") (pinfunction "2_2") (pintype "passive"))
      (node (ref "Q2") (pin "3") (pinfunction "S_3") (pintype "passive"))
      (node (ref "Q4") (pin "3") (pinfunction "S_3") (pintype "passive"))
      (node (ref "Q6") (pin "3") (pinfunction "S_3") (pintype "passive"))
      (node (ref "R321") (pin "1") (pinfunction "1_1") (pintype "passive"))
      (node (ref "R341") (pin "1") (pinfunction "1_1") (pintype "passive"))
    )
    (net (code "30") (name "/PHASE_U") (class "Default")
      (node (ref "C6") (pin "1") (pinfunction "1_1") (pintype "passive"))
      (node (ref "DRIVE") (pin "18") (pinfunction "VS1_18") (pintype "passive"))
      (node (ref "Q1") (pin "3") (pinfunction "S_3") (pintype "passive"))
      (node (ref "Q2") (pin "1") (pinfunction "D_1") (pintype "passive"))
      (node (ref "R331") (pin "1") (pinfunction "1_1") (pintype "passive"))
      (node (ref "R334") (pin "1") (pinfunction "1_1") (pintype "passive"))
      (node (ref "U") (pin "1") (pinfunction "1_1") (pintype "passive"))
    )
    (net (code "31") (name "/PHASE_V") (class "Default")
      (node (ref "C10") (pin "1") (pinfunction "1_1") (pintype "passive"))
      (node (ref "DRIVE") (pin "15") (pinfunction "VS2_15") (pintype "passive"))
      (node (ref "Q3") (pin "3") (pinfunction "S_3") (pintype "passive"))
      (node (ref "Q4") (pin "1") (pinfunction "D_1") (pintype "passive"))
      (node (ref "R332") (pin "1") (pinfunction "1_1") (pintype "passive"))
      (node (ref "R345") (pin "1") (pinfunction "1_1") (pintype "passive"))
      (node (ref "V") (pin "1") (pinfunction "1_1") (pintype "passive"))
    )
    (net (code "32") (name "/PHASE_W") (class "Default")
      (node (ref "C15") (pin "1") (pinfunction "1_1") (pintype "passive"))
      (node (ref "DRIVE") (pin "12") (pinfunction "VS3_12") (pintype "passive"))
      (node (ref "Q5") (pin "3") (pinfunction "S_3") (pintype "passive"))
      (node (ref "Q6") (pin "1") (pinfunction "D_1") (pintype "passive"))
      (node (ref "R333") (pin "1") (pinfunction "1_1") (pintype "passive"))
      (node (ref "R336") (pin "1") (pinfunction "1_1") (pintype "passive"))
      (node (ref "W") (pin "1") (pinfunction "1_1") (pintype "passive"))
    )
    (net (code "33") (name "/SENS_U") (class "Default")
      (node (ref "LM339") (pin "2") (pinfunction "O1_2") (pintype "passive"))
      (node (ref "MCU") (pin "28") (pinfunction "PB5_28") (pintype "passive"))
    )
    (net (code "34") (name "/SENS_V") (class "Default")
      (node (ref "LM339") (pin "1") (pinfunction "O2_1") (pintype "passive"))
      (node (ref "MCU") (pin "29") (pinfunction "PB6_29") (pintype "passive"))
    )
    (net (code "35") (name "/SENS_W") (class "Default")
      (node (ref "LM339") (pin "14") (pinfunction "O3_14") (pintype "passive"))
      (node (ref "MCU") (pin "30") (pinfunction "PB7_30") (pintype "passive"))
    )
    (net (code "36") (name "/THR_ADC") (class "Default")
      (node (ref "MCU") (pin "10") (pinfunction "PA4_10") (pintype "passive"))
      (node (ref "R34") (pin "1") (pinfunction "1_1") (pintype "passive"))
      (node (ref "R35") (pin "2") (pinfunction "2_2") (pintype "passive"))
    )
    (net (code "37") (name "/THR_RAW") (class "Default")
      (node (ref "R35") (pin "1") (pinfunction "1_1") (pintype "passive"))
      (node (ref "THROTTLE") (pin "3") (pinfunction "3_3") (pintype "passive"))
    )
    (net (code "38") (name "/UART_RX") (class "Default")
      (node (ref "EXT") (pin "4") (pinfunction "4_4") (pintype "passive"))
      (node (ref "MCU") (pin "25") (pinfunction "PA15_25") (pintype "passive"))
    )
    (net (code "39") (name "/UART_TX") (class "Default")
      (node (ref "EXT") (pin "3") (pinfunction "3_3") (pintype "passive"))
      (node (ref "MCU") (pin "24") (pinfunction "PA14_24") (pintype "passive"))
    )
    (net (code "40") (name "/VB1") (class "Default")
      (node (ref "C6") (pin "2") (pinfunction "2_2") (pintype "passive"))
      (node (ref "D1") (pin "2") (pinfunction "K_2") (pintype "passive"))
      (node (ref "DRIVE") (pin "20") (pinfunction "VB1_20") (pintype "passive"))
    )
    (net (code "41") (name "/VB2") (class "Default")
      (node (ref "C10") (pin "2") (pinfunction "2_2") (pintype "passive"))
      (node (ref "D2") (pin "2") (pinfunction "K_2") (pintype "passive"))
      (node (ref "DRIVE") (pin "17") (pinfunction "VB2_17") (pintype "passive"))
    )
    (net (code "42") (name "/VB3") (class "Default")
      (node (ref "C15") (pin "2") (pinfunction "2_2") (pintype "passive"))
      (node (ref "D3") (pin "2") (pinfunction "K_2") (pintype "passive"))
      (node (ref "DRIVE") (pin "14") (pinfunction "VB3_14") (pintype "passive"))
    )
    (net (code "43") (name "/Vref") (class "Default")
      (node (ref "C71") (pin "2") (pinfunction "2_2") (pintype "passive"))
      (node (ref "C8") (pin "2") (pinfunction "2_2") (pintype "passive"))
      (node (ref "C9") (pin "2") (pinfunction "2_2") (pintype "passive"))
      (node (ref "LM339") (pin "4") (pinfunction "I1-_4") (pintype "passive"))
      (node (ref "LM339") (pin "6") (pinfunction "I2-_6") (pintype "passive"))
      (node (ref "LM339") (pin "8") (pinfunction "I3-_8") (pintype "passive"))
      (node (ref "R1231") (pin "1") (pinfunction "1_1") (pintype "passive"))
      (node (ref "R331") (pin "2") (pinfunction "2_2") (pintype "passive"))
      (node (ref "R332") (pin "2") (pinfunction "2_2") (pintype "passive"))
      (node (ref "R333") (pin "2") (pinfunction "2_2") (pintype "passive"))
    )
    (net (code "44") (name "GND") (class "Default")
      (node (ref "C11") (pin "2") (pinfunction "2_2") (pintype "passive"))
      (node (ref "C12") (pin "2") (pinfunction "2_2") (pintype "passive"))
      (node (ref "C1234") (pin "2") (pinfunction "2_2") (pintype "passive"))
      (node (ref "C1235") (pin "2") (pinfunction "2_2") (pintype "passive"))
      (node (ref "C14") (pin "1") (pinfunction "1_1") (pintype "passive"))
      (node (ref "C223") (pin "2") (pinfunction "2_2") (pintype "passive"))
      (node (ref "C2234") (pin "2") (pinfunction "2_2") (pintype "passive"))
      (node (ref "C23") (pin "2") (pinfunction "2_2") (pintype "passive"))
      (node (ref "C26") (pin "1") (pinfunction "1_1") (pintype "passive"))
      (node (ref "C28") (pin "2") (pinfunction "2_2") (pintype "passive"))
      (node (ref "C3") (pin "2") (pinfunction "2_2") (pintype "passive"))
      (node (ref "C30") (pin "2") (pinfunction "2_2") (pintype "passive"))
      (node (ref "C31") (pin "2") (pinfunction "2_2") (pintype "passive"))
      (node (ref "C32") (pin "2") (pinfunction "2_2") (pintype "passive"))
      (node (ref "C4") (pin "1") (pinfunction "1_1") (pintype "passive"))
      (node (ref "C42") (pin "2") (pinfunction "2_2") (pintype "passive"))
      (node (ref "C43") (pin "2") (pinfunction "2_2") (pintype "passive"))
      (node (ref "C66") (pin "2") (pinfunction "2_2") (pintype "passive"))
      (node (ref "D4") (pin "1") (pinfunction "A_1") (pintype "passive"))
      (node (ref "D5") (pin "1") (pinfunction "A_1") (pintype "passive"))
      (node (ref "D6") (pin "1") (pinfunction "A_1") (pintype "passive"))
      (node (ref "DRIVE") (pin "8") (pinfunction "GND_8") (pintype "passive"))
      (node (ref "EXT") (pin "2") (pinfunction "2_2") (pintype "passive"))
      (node (ref "FAN") (pin "2") (pinfunction "2_2") (pintype "passive"))
      (node (ref "HALL") (pin "2") (pinfunction "2_2") (pintype "passive"))
      (node (ref "LDO1") (pin "2") (pinfunction "GND_2") (pintype "passive"))
      (node (ref "LDO2") (pin "1") (pinfunction "GND_1") (pintype "passive"))
      (node (ref "LM321") (pin "2") (pinfunction "V-_2") (pintype "passive"))
      (node (ref "LM339") (pin "12") (pinfunction "VSS_12") (pintype "passive"))
      (node (ref "MCU") (pin "16") (pinfunction "VSS_16") (pintype "passive"))
      (node (ref "MCU") (pin "31") (pinfunction "BOOT0_31") (pintype "passive"))
      (node (ref "MCU") (pin "32") (pinfunction "VSS_32") (pintype "passive"))
      (node (ref "MP2459") (pin "2") (pinfunction "GND_2") (pintype "passive"))
      (node (ref "R123") (pin "2") (pinfunction "2_2") (pintype "passive"))
      (node (ref "R1231") (pin "2") (pinfunction "2_2") (pintype "passive"))
      (node (ref "R24") (pin "2") (pinfunction "2_2") (pintype "passive"))
      (node (ref "R30") (pin "1") (pinfunction "1_1") (pintype "passive"))
      (node (ref "R321") (pin "2") (pinfunction "2_2") (pintype "passive"))
      (node (ref "R33") (pin "2") (pinfunction "2_2") (pintype "passive"))
      (node (ref "R34") (pin "2") (pinfunction "2_2") (pintype "passive"))
      (node (ref "R351") (pin "1") (pinfunction "1_1") (pintype "passive"))
      (node (ref "R352") (pin "1") (pinfunction "1_1") (pintype "passive"))
      (node (ref "R354") (pin "1") (pinfunction "1_1") (pintype "passive"))
      (node (ref "SW") (pin "3") (pinfunction "3_3") (pintype "passive"))
      (node (ref "THROTTLE") (pin "2") (pinfunction "2_2") (pintype "passive"))
      (node (ref "V-") (pin "1") (pinfunction "1_1") (pintype "passive"))
    )
    (net (code "45") (name "Net-(C51-Pad2)") (class "Default")
      (node (ref "C51") (pin "2") (pinfunction "2_2") (pintype "passive"))
      (node (ref "C52") (pin "1") (pinfunction "1_1") (pintype "passive"))
    )
    (net (code "46") (name "Net-(C53-Pad1)") (class "Default")
      (node (ref "C53") (pin "1") (pinfunction "1_1") (pintype "passive"))
      (node (ref "C54") (pin "2") (pinfunction "2_2") (pintype "passive"))
    )
    (net (code "47") (name "Net-(D4-K)") (class "Default")
      (node (ref "C123") (pin "2") (pinfunction "2_2") (pintype "passive"))
      (node (ref "D4") (pin "2") (pinfunction "K_2") (pintype "passive"))
      (node (ref "L1") (pin "1") (pinfunction "1_1") (pintype "passive"))
      (node (ref "MP2459") (pin "6") (pinfunction "SW_6") (pintype "passive"))
    )
    (net (code "48") (name "Net-(LED-K)") (class "Default")
      (node (ref "LED") (pin "2") (pinfunction "K_2") (pintype "passive"))
      (node (ref "R24") (pin "1") (pinfunction "1_1") (pintype "passive"))
    )
    (net (code "49") (name "Net-(LM321-+IN)") (class "Default")
      (node (ref "C223") (pin "1") (pinfunction "1_1") (pintype "passive"))
      (node (ref "LM321") (pin "1") (pinfunction "+IN_1") (pintype "passive"))
      (node (ref "R341") (pin "2") (pinfunction "2_2") (pintype "passive"))
    )
    (net (code "50") (name "Net-(LM321--IN)") (class "Default")
      (node (ref "LM321") (pin "3") (pinfunction "-IN_3") (pintype "passive"))
      (node (ref "R28") (pin "1") (pinfunction "1_1") (pintype "passive"))
      (node (ref "R30") (pin "2") (pinfunction "2_2") (pintype "passive"))
    )
    (net (code "51") (name "Net-(MCU-NRST)") (class "Default")
      (node (ref "C26") (pin "2") (pinfunction "2_2") (pintype "passive"))
      (node (ref "MCU") (pin "4") (pinfunction "NRST_4") (pintype "passive"))
    )
    (net (code "52") (name "Net-(MP2459-BST)") (class "Default")
      (node (ref "C123") (pin "1") (pinfunction "1_1") (pintype "passive"))
      (node (ref "MP2459") (pin "1") (pinfunction "BST_1") (pintype "passive"))
    )
    (net (code "53") (name "Net-(MP2459-EN)") (class "Default")
      (node (ref "MP2459") (pin "4") (pinfunction "EN_4") (pintype "passive"))
      (node (ref "R23") (pin "2") (pinfunction "2_2") (pintype "passive"))
    )
    (net (code "54") (name "Net-(MP2459-FB)") (class "Default")
      (node (ref "MP2459") (pin "3") (pinfunction "FB_3") (pintype "passive"))
      (node (ref "R123") (pin "1") (pinfunction "1_1") (pintype "passive"))
      (node (ref "R231") (pin "1") (pinfunction "1_1") (pintype "passive"))
    )
    (net (code "55") (name "Net-(Q1-G)") (class "Default")
      (node (ref "Q1") (pin "2") (pinfunction "G_2") (pintype "passive"))
      (node (ref "R10") (pin "1") (pinfunction "1_1") (pintype "passive"))
    )
    (net (code "56") (name "Net-(Q2-G)") (class "Default")
      (node (ref "Q2") (pin "2") (pinfunction "G_2") (pintype "passive"))
      (node (ref "R18") (pin "1") (pinfunction "1_1") (pintype "passive"))
    )
    (net (code "57") (name "Net-(Q3-G)") (class "Default")
      (node (ref "Q3") (pin "2") (pinfunction "G_2") (pintype "passive"))
      (node (ref "R11") (pin "1") (pinfunction "1_1") (pintype "passive"))
    )
    (net (code "58") (name "Net-(Q4-G)") (class "Default")
      (node (ref "Q4") (pin "2") (pinfunction "G_2") (pintype "passive"))
      (node (ref "R16") (pin "1") (pinfunction "1_1") (pintype "passive"))
    )
    (net (code "59") (name "Net-(Q5-G)") (class "Default")
      (node (ref "Q5") (pin "2") (pinfunction "G_2") (pintype "passive"))
      (node (ref "R9") (pin "1") (pinfunction "1_1") (pintype "passive"))
    )
    (net (code "60") (name "Net-(Q6-G)") (class "Default")
      (node (ref "Q6") (pin "2") (pinfunction "G_2") (pintype "passive"))
      (node (ref "R17") (pin "1") (pinfunction "1_1") (pintype "passive"))
    )
    (net (code "61") (name "VBAT") (class "Default")
      (node (ref "C51") (pin "1") (pinfunction "1_1") (pintype "passive"))
      (node (ref "C54") (pin "1") (pinfunction "1_1") (pintype "passive"))
      (node (ref "Q1") (pin "1") (pinfunction "D_1") (pintype "passive"))
      (node (ref "Q3") (pin "1") (pinfunction "D_1") (pintype "passive"))
      (node (ref "Q5") (pin "1") (pinfunction "D_1") (pintype "passive"))
      (node (ref "SW") (pin "1") (pinfunction "1_1") (pintype "passive"))
      (node (ref "V+") (pin "1") (pinfunction "1_1") (pintype "passive"))
    )
    (net (code "62") (name "unconnected-(DRIVE-LO2-Pad10)") (class "Default")
      (node (ref "DRIVE") (pin "10") (pinfunction "LO2_10") (pintype "passive"))
    )
    (net (code "63") (name "unconnected-(MCU-PA2-Pad8)") (class "Default")
      (node (ref "MCU") (pin "8") (pinfunction "PA2_8") (pintype "passive"))
    )
    (net (code "64") (name "unconnected-(MCU-PA3-Pad9)") (class "Default")
      (node (ref "MCU") (pin "9") (pinfunction "PA3_9") (pintype "passive"))
    )
    (net (code "65") (name "unconnected-(MCU-PA5-Pad11)") (class "Default")
      (node (ref "MCU") (pin "11") (pinfunction "PA5_11") (pintype "passive"))
    )
    (net (code "66") (name "unconnected-(MCU-PB3-Pad26)") (class "Default")
      (node (ref "MCU") (pin "26") (pinfunction "PB3_26") (pintype "passive"))
    )
    (net (code "67") (name "unconnected-(MCU-PF1-Pad3)") (class "Default")
      (node (ref "MCU") (pin "3") (pinfunction "PF1_3") (pintype "passive"))
    )
  )
)
